# core3.net
KiCad netlist of a schematic drawn in EAGLE
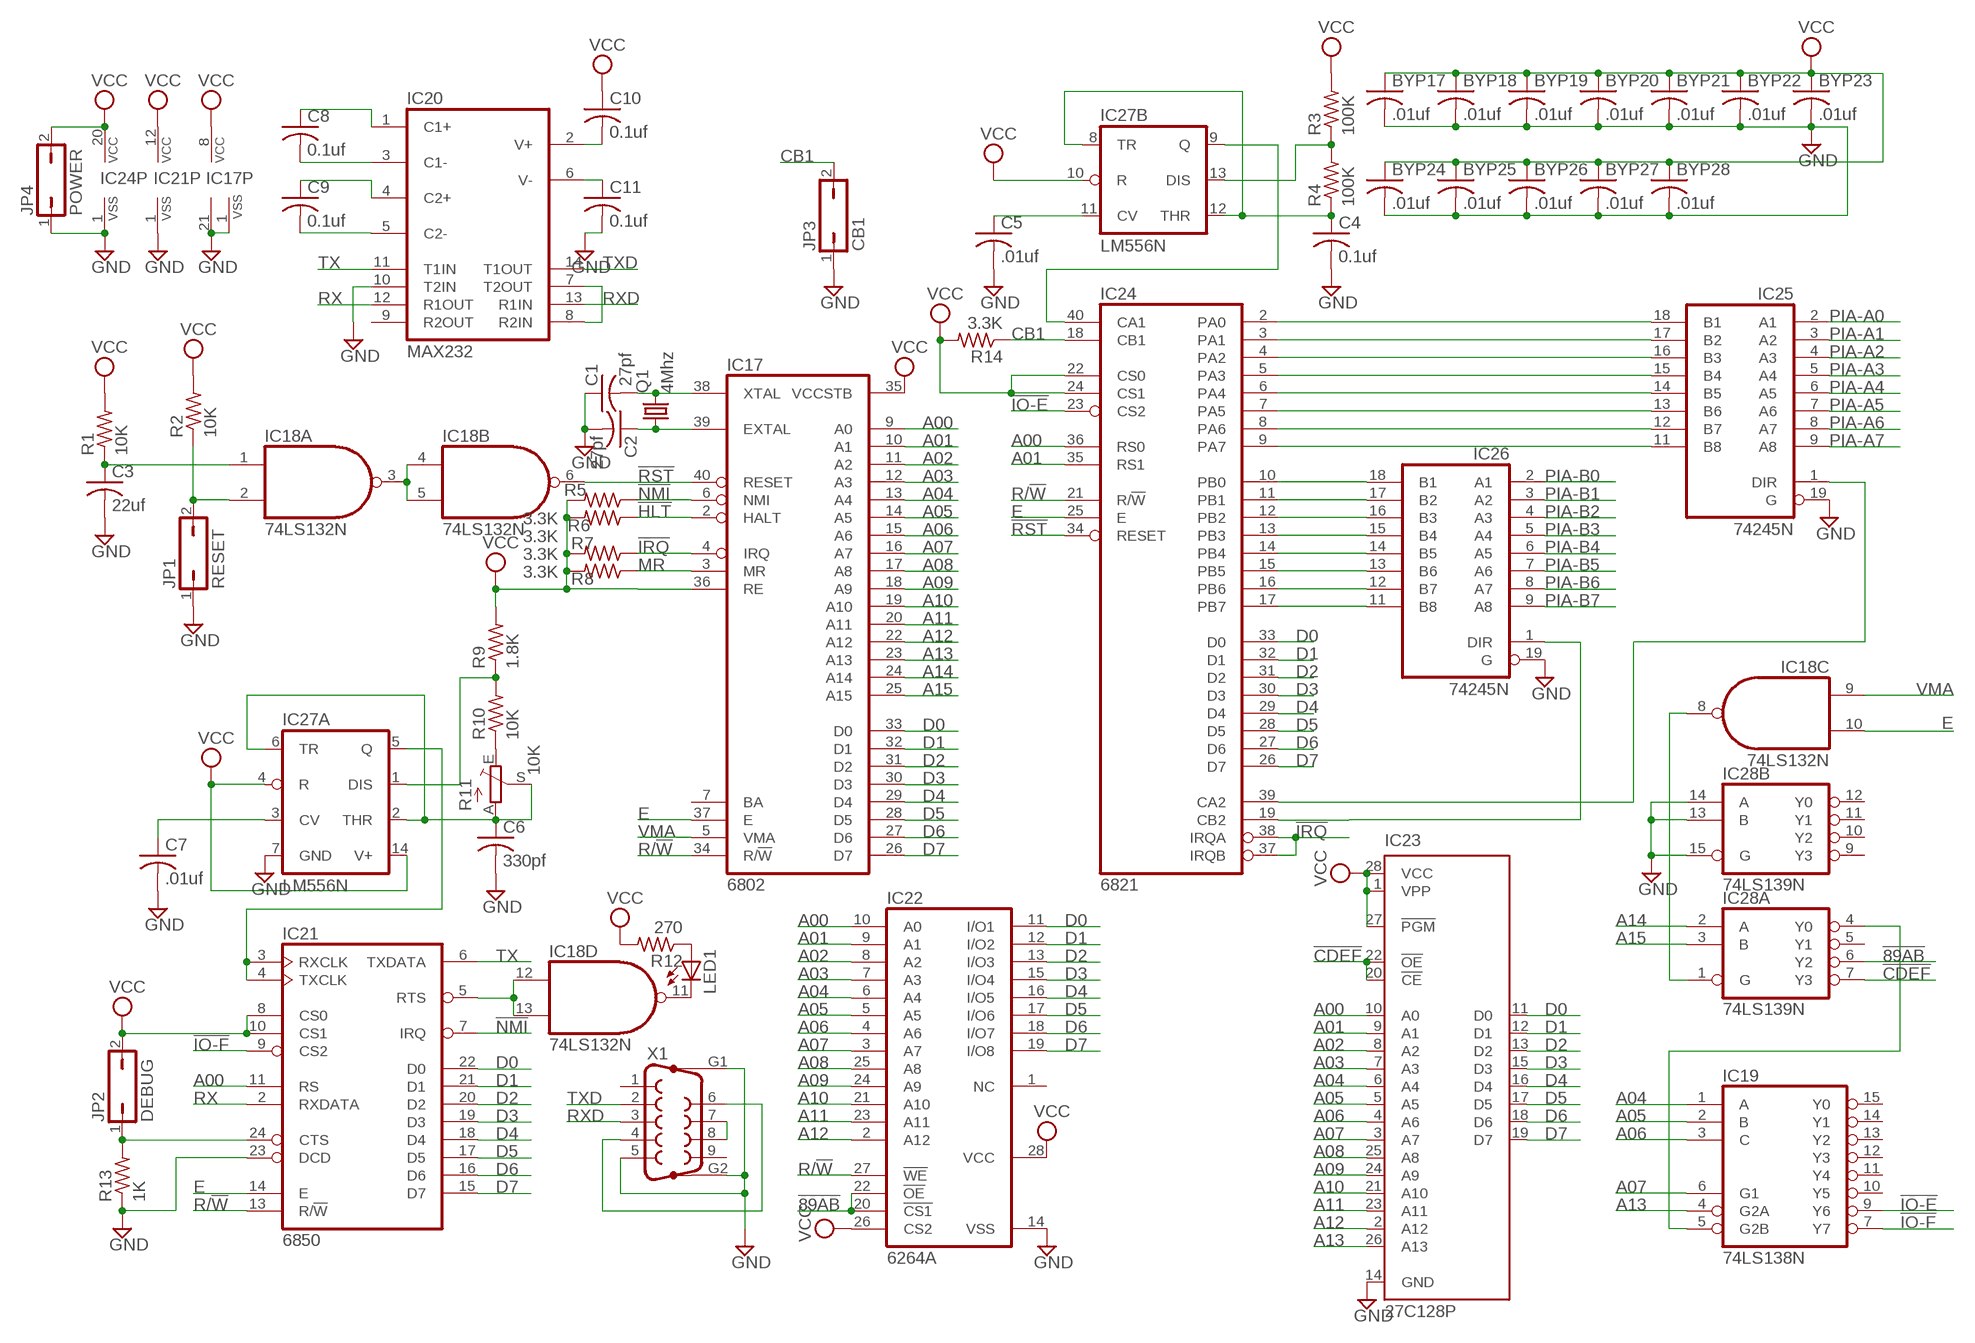
[diagram p0: schematic, sheet 1]
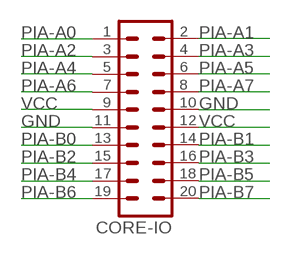
[diagram p1: schematic, sheet 2]

(export (version "E")
  (design (tool "Eeschema 10.0.6"))
  (components
    (comp (ref "BYP17")
      (value ".01uf")
      (footprint "eagle-import:C050-025X075")
      (libsource (lib "eagle-import") (part "C-US050-025X075"))
    )
    (comp (ref "BYP18")
      (value ".01uf")
      (footprint "eagle-import:C050-025X075")
      (libsource (lib "eagle-import") (part "C-US050-025X075"))
    )
    (comp (ref "BYP19")
      (value ".01uf")
      (footprint "eagle-import:C050-025X075")
      (libsource (lib "eagle-import") (part "C-US050-025X075"))
    )
    (comp (ref "BYP20")
      (value ".01uf")
      (footprint "eagle-import:C050-025X075")
      (libsource (lib "eagle-import") (part "C-US050-025X075"))
    )
    (comp (ref "BYP21")
      (value ".01uf")
      (footprint "eagle-import:C050-025X075")
      (libsource (lib "eagle-import") (part "C-US050-025X075"))
    )
    (comp (ref "BYP22")
      (value ".01uf")
      (footprint "eagle-import:C050-025X075")
      (libsource (lib "eagle-import") (part "C-US050-025X075"))
    )
    (comp (ref "BYP23")
      (value ".01uf")
      (footprint "eagle-import:C050-025X075")
      (libsource (lib "eagle-import") (part "C-US050-025X075"))
    )
    (comp (ref "BYP24")
      (value ".01uf")
      (footprint "eagle-import:C050-025X075")
      (libsource (lib "eagle-import") (part "C-US050-025X075"))
    )
    (comp (ref "BYP25")
      (value ".01uf")
      (footprint "eagle-import:C050-025X075")
      (libsource (lib "eagle-import") (part "C-US050-025X075"))
    )
    (comp (ref "BYP26")
      (value ".01uf")
      (footprint "eagle-import:C050-025X075")
      (libsource (lib "eagle-import") (part "C-US050-025X075"))
    )
    (comp (ref "BYP27")
      (value ".01uf")
      (footprint "eagle-import:C050-025X075")
      (libsource (lib "eagle-import") (part "C-US050-025X075"))
    )
    (comp (ref "BYP28")
      (value ".01uf")
      (footprint "eagle-import:C050-025X075")
      (libsource (lib "eagle-import") (part "C-US050-025X075"))
    )
    (comp (ref "C1")
      (value "27pf")
      (footprint "eagle-import:C050-025X075")
      (libsource (lib "eagle-import") (part "C-US050-025X075"))
    )
    (comp (ref "C2")
      (value "27pf")
      (footprint "eagle-import:C050-025X075")
      (libsource (lib "eagle-import") (part "C-US050-025X075"))
    )
    (comp (ref "C3")
      (value "22uf")
      (footprint "eagle-import:C102-043X133")
      (libsource (lib "eagle-import") (part "C-US102-043X133"))
    )
    (comp (ref "C4")
      (value "0.1uf")
      (footprint "eagle-import:C050-025X075")
      (libsource (lib "eagle-import") (part "C-US050-025X075"))
    )
    (comp (ref "C5")
      (value ".01uf")
      (footprint "eagle-import:C050-025X075")
      (libsource (lib "eagle-import") (part "C-US050-025X075"))
    )
    (comp (ref "C6")
      (value "330pf")
      (footprint "eagle-import:C050-025X075")
      (libsource (lib "eagle-import") (part "C-US050-025X075"))
    )
    (comp (ref "C7")
      (value ".01uf")
      (footprint "eagle-import:C050-025X075")
      (libsource (lib "eagle-import") (part "C-US050-025X075"))
    )
    (comp (ref "C8")
      (value "0.1uf")
      (footprint "eagle-import:C050-025X075")
      (libsource (lib "eagle-import") (part "C-US050-025X075"))
    )
    (comp (ref "C9")
      (value "0.1uf")
      (footprint "eagle-import:C050-025X075")
      (libsource (lib "eagle-import") (part "C-US050-025X075"))
    )
    (comp (ref "C10")
      (value "0.1uf")
      (footprint "eagle-import:C050-025X075")
      (libsource (lib "eagle-import") (part "C-US050-025X075"))
    )
    (comp (ref "C11")
      (value "0.1uf")
      (footprint "eagle-import:C050-025X075")
      (libsource (lib "eagle-import") (part "C-US050-025X075"))
    )
    (comp (ref "IC17")
      (value "6802")
      (footprint "eagle-import:DIL40")
      (libsource (lib "eagle-import") (part "6802"))
    )
    (comp (ref "IC18")
      (value "74LS132N")
      (footprint "eagle-import:DIL14")
      (libsource (lib "eagle-import") (part "7400NLS"))
    )
    (comp (ref "IC19")
      (value "74LS138N")
      (footprint "eagle-import:DIL16")
      (libsource (lib "eagle-import") (part "74138NLS"))
    )
    (comp (ref "IC20")
      (value "MAX232")
      (footprint "eagle-import:DIL16")
      (fields (field (name "MF") "MAXIM") (field (name "MPN") "MAX232ACPE+"))
      (libsource (lib "eagle-import") (part "MAX232"))
    )
    (comp (ref "IC21")
      (value "6850")
      (footprint "eagle-import:DIL24")
      (fields (field (name "MF") "NTE ELECTRONICS") (field (name "MPN") "NTE6850"))
      (libsource (lib "eagle-import") (part "6850"))
    )
    (comp (ref "IC22")
      (value "6264A")
      (footprint "eagle-import:DIL28-6")
      (libsource (lib "eagle-import") (part "6264A"))
    )
    (comp (ref "IC23")
      (value "27C128P")
      (footprint "eagle-import:DIL28-6")
      (libsource (lib "eagle-import") (part "27128PC"))
    )
    (comp (ref "IC24")
      (value "6821")
      (footprint "eagle-import:DIL40")
      (fields (field (name "MF") "NTE ELECTRONICS") (field (name "MPN") "NTE6821"))
      (libsource (lib "eagle-import") (part "6821"))
    )
    (comp (ref "IC25")
      (value "74245N")
      (footprint "eagle-import:DIL20")
      (libsource (lib "eagle-import") (part "74245NLS"))
    )
    (comp (ref "IC26")
      (value "74245N")
      (footprint "eagle-import:DIL20")
      (libsource (lib "eagle-import") (part "74245NLS"))
    )
    (comp (ref "IC27")
      (value "LM556N")
      (footprint "eagle-import:DIL14")
      (libsource (lib "eagle-import") (part "556NLM"))
    )
    (comp (ref "IC28")
      (value "74LS139N")
      (footprint "eagle-import:DIL16")
      (libsource (lib "eagle-import") (part "74139NLS"))
    )
    (comp (ref "JP1")
      (value "RESET")
      (footprint "eagle-import:JP1")
      (libsource (lib "eagle-import") (part "JP1Q"))
    )
    (comp (ref "JP2")
      (value "DEBUG")
      (footprint "eagle-import:JP1")
      (libsource (lib "eagle-import") (part "JP1Q"))
    )
    (comp (ref "JP3")
      (value "CB1")
      (footprint "eagle-import:JP1")
      (libsource (lib "eagle-import") (part "JP1Q"))
    )
    (comp (ref "JP4")
      (value "POWER")
      (footprint "eagle-import:JP1")
      (libsource (lib "eagle-import") (part "JP1Q"))
    )
    (comp (ref "LED1")
      (value "LED3MM")
      (footprint "eagle-import:LED3MM")
      (libsource (lib "eagle-import") (part "LED3MM"))
    )
    (comp (ref "Q1")
      (value "4Mhz")
      (footprint "eagle-import:HC18U-V")
      (libsource (lib "eagle-import") (part "CRYSTALHC18U-V"))
    )
    (comp (ref "R1")
      (value "10K")
      (footprint "eagle-import:0207_7")
      (libsource (lib "eagle-import") (part "R-US_0207/7"))
    )
    (comp (ref "R2")
      (value "10K")
      (footprint "eagle-import:0207_7")
      (libsource (lib "eagle-import") (part "R-US_0207/7"))
    )
    (comp (ref "R3")
      (value "100K")
      (footprint "eagle-import:0207_7")
      (libsource (lib "eagle-import") (part "R-US_0207/7"))
    )
    (comp (ref "R4")
      (value "100K")
      (footprint "eagle-import:0207_7")
      (libsource (lib "eagle-import") (part "R-US_0207/7"))
    )
    (comp (ref "R5")
      (value "3.3K")
      (footprint "eagle-import:0207_7")
      (libsource (lib "eagle-import") (part "R-US_0207/7"))
    )
    (comp (ref "R6")
      (value "3.3K")
      (footprint "eagle-import:0207_7")
      (libsource (lib "eagle-import") (part "R-US_0207/7"))
    )
    (comp (ref "R7")
      (value "3.3K")
      (footprint "eagle-import:0207_7")
      (libsource (lib "eagle-import") (part "R-US_0207/7"))
    )
    (comp (ref "R8")
      (value "3.3K")
      (footprint "eagle-import:0207_7")
      (libsource (lib "eagle-import") (part "R-US_0207/7"))
    )
    (comp (ref "R9")
      (value "1.8K")
      (footprint "eagle-import:0207_7")
      (libsource (lib "eagle-import") (part "R-US_0207/7"))
    )
    (comp (ref "R10")
      (value "10K")
      (footprint "eagle-import:0207_7")
      (libsource (lib "eagle-import") (part "R-US_0207/7"))
    )
    (comp (ref "R11")
      (value "10K")
      (footprint "eagle-import:SP19L")
      (libsource (lib "eagle-import") (part "TRIM_EU-B90P"))
    )
    (comp (ref "R12")
      (value "270")
      (footprint "eagle-import:0207_7")
      (libsource (lib "eagle-import") (part "R-US_0207/7"))
    )
    (comp (ref "R13")
      (value "1K")
      (footprint "eagle-import:0207_7")
      (libsource (lib "eagle-import") (part "R-US_0207/7"))
    )
    (comp (ref "R14")
      (value "3.3K")
      (footprint "eagle-import:0207_7")
      (libsource (lib "eagle-import") (part "R-US_0207/7"))
    )
    (comp (ref "X1")
      (value "F09HP")
      (footprint "eagle-import:F09HP")
      (libsource (lib "eagle-import") (part "F09HP"))
    )
    (comp (ref "CORE-IO")
      (value "MA10-2")
      (footprint "eagle-import:MA10-2")
      (libsource (lib "eagle-import") (part "MA10-2"))
    )
  )
  (nets
    (net (code "1") (name "A00") (class "Default")
      (node (ref "IC17") (pin "9") (pinfunction "A0_9") (pintype "output"))
      (node (ref "IC21") (pin "11") (pinfunction "RS_11") (pintype "input"))
      (node (ref "IC22") (pin "10") (pinfunction "A0_10") (pintype "input"))
      (node (ref "IC23") (pin "10") (pinfunction "A0_10") (pintype "input"))
      (node (ref "IC24") (pin "36") (pinfunction "RS0_36") (pintype "input"))
    )
    (net (code "2") (name "A01") (class "Default")
      (node (ref "IC17") (pin "10") (pinfunction "A1_10") (pintype "output"))
      (node (ref "IC22") (pin "9") (pinfunction "A1_9") (pintype "input"))
      (node (ref "IC23") (pin "9") (pinfunction "A1_9") (pintype "input"))
      (node (ref "IC24") (pin "35") (pinfunction "RS1_35") (pintype "input"))
    )
    (net (code "3") (name "A02") (class "Default")
      (node (ref "IC17") (pin "11") (pinfunction "A2_11") (pintype "output"))
      (node (ref "IC22") (pin "8") (pinfunction "A2_8") (pintype "input"))
      (node (ref "IC23") (pin "8") (pinfunction "A2_8") (pintype "input"))
    )
    (net (code "4") (name "A03") (class "Default")
      (node (ref "IC17") (pin "12") (pinfunction "A3_12") (pintype "output"))
      (node (ref "IC22") (pin "7") (pinfunction "A3_7") (pintype "input"))
      (node (ref "IC23") (pin "7") (pinfunction "A3_7") (pintype "input"))
    )
    (net (code "5") (name "A04") (class "Default")
      (node (ref "IC17") (pin "13") (pinfunction "A4_13") (pintype "output"))
      (node (ref "IC19") (pin "1") (pinfunction "A_1") (pintype "input"))
      (node (ref "IC22") (pin "6") (pinfunction "A4_6") (pintype "input"))
      (node (ref "IC23") (pin "6") (pinfunction "A4_6") (pintype "input"))
    )
    (net (code "6") (name "A05") (class "Default")
      (node (ref "IC17") (pin "14") (pinfunction "A5_14") (pintype "output"))
      (node (ref "IC19") (pin "2") (pinfunction "B_2") (pintype "input"))
      (node (ref "IC22") (pin "5") (pinfunction "A5_5") (pintype "input"))
      (node (ref "IC23") (pin "5") (pinfunction "A5_5") (pintype "input"))
    )
    (net (code "7") (name "A06") (class "Default")
      (node (ref "IC17") (pin "15") (pinfunction "A6_15") (pintype "output"))
      (node (ref "IC19") (pin "3") (pinfunction "C_3") (pintype "input"))
      (node (ref "IC22") (pin "4") (pinfunction "A6_4") (pintype "input"))
      (node (ref "IC23") (pin "4") (pinfunction "A6_4") (pintype "input"))
    )
    (net (code "8") (name "A07") (class "Default")
      (node (ref "IC17") (pin "16") (pinfunction "A7_16") (pintype "output"))
      (node (ref "IC19") (pin "6") (pinfunction "G1_6") (pintype "input"))
      (node (ref "IC22") (pin "3") (pinfunction "A7_3") (pintype "input"))
      (node (ref "IC23") (pin "3") (pinfunction "A7_3") (pintype "input"))
    )
    (net (code "9") (name "A08") (class "Default")
      (node (ref "IC17") (pin "17") (pinfunction "A8_17") (pintype "output"))
      (node (ref "IC22") (pin "25") (pinfunction "A8_25") (pintype "input"))
      (node (ref "IC23") (pin "25") (pinfunction "A8_25") (pintype "input"))
    )
    (net (code "10") (name "A09") (class "Default")
      (node (ref "IC17") (pin "18") (pinfunction "A9_18") (pintype "output"))
      (node (ref "IC22") (pin "24") (pinfunction "A9_24") (pintype "input"))
      (node (ref "IC23") (pin "24") (pinfunction "A9_24") (pintype "input"))
    )
    (net (code "11") (name "A10") (class "Default")
      (node (ref "IC17") (pin "19") (pinfunction "A10_19") (pintype "output"))
      (node (ref "IC22") (pin "21") (pinfunction "A10_21") (pintype "input"))
      (node (ref "IC23") (pin "21") (pinfunction "A10_21") (pintype "input"))
    )
    (net (code "12") (name "A11") (class "Default")
      (node (ref "IC17") (pin "20") (pinfunction "A11_20") (pintype "output"))
      (node (ref "IC22") (pin "23") (pinfunction "A11_23") (pintype "input"))
      (node (ref "IC23") (pin "23") (pinfunction "A11_23") (pintype "input"))
    )
    (net (code "13") (name "A12") (class "Default")
      (node (ref "IC17") (pin "22") (pinfunction "A12_22") (pintype "output"))
      (node (ref "IC22") (pin "2") (pinfunction "A12_2") (pintype "input"))
      (node (ref "IC23") (pin "2") (pinfunction "A12_2") (pintype "input"))
    )
    (net (code "14") (name "A13") (class "Default")
      (node (ref "IC17") (pin "23") (pinfunction "A13_23") (pintype "output"))
      (node (ref "IC19") (pin "4") (pinfunction "G2A_4") (pintype "input"))
      (node (ref "IC23") (pin "26") (pinfunction "A13_26") (pintype "input"))
    )
    (net (code "15") (name "A14") (class "Default")
      (node (ref "IC17") (pin "24") (pinfunction "A14_24") (pintype "output"))
      (node (ref "IC28") (pin "2") (pinfunction "A_2") (pintype "input"))
    )
    (net (code "16") (name "A15") (class "Default")
      (node (ref "IC17") (pin "25") (pinfunction "A15_25") (pintype "output"))
      (node (ref "IC28") (pin "3") (pinfunction "B_3") (pintype "input"))
    )
    (net (code "17") (name "CB1") (class "Default")
      (node (ref "IC24") (pin "18") (pinfunction "CB1_18") (pintype "input"))
      (node (ref "JP3") (pin "2") (pinfunction "2_2") (pintype "passive"))
      (node (ref "R14") (pin "1") (pinfunction "1_1") (pintype "passive"))
    )
    (net (code "18") (name "D0") (class "Default")
      (node (ref "IC17") (pin "33") (pinfunction "D0_33") (pintype "bidirectional"))
      (node (ref "IC21") (pin "22") (pinfunction "D0_22") (pintype "bidirectional"))
      (node (ref "IC22") (pin "11") (pinfunction "I/O1_11") (pintype "bidirectional"))
      (node (ref "IC23") (pin "11") (pinfunction "D0_11") (pintype "tri_state"))
      (node (ref "IC24") (pin "33") (pinfunction "D0_33") (pintype "bidirectional"))
    )
    (net (code "19") (name "D1") (class "Default")
      (node (ref "IC17") (pin "32") (pinfunction "D1_32") (pintype "bidirectional"))
      (node (ref "IC21") (pin "21") (pinfunction "D1_21") (pintype "bidirectional"))
      (node (ref "IC22") (pin "12") (pinfunction "I/O2_12") (pintype "bidirectional"))
      (node (ref "IC23") (pin "12") (pinfunction "D1_12") (pintype "tri_state"))
      (node (ref "IC24") (pin "32") (pinfunction "D1_32") (pintype "bidirectional"))
    )
    (net (code "20") (name "D2") (class "Default")
      (node (ref "IC17") (pin "31") (pinfunction "D2_31") (pintype "bidirectional"))
      (node (ref "IC21") (pin "20") (pinfunction "D2_20") (pintype "bidirectional"))
      (node (ref "IC22") (pin "13") (pinfunction "I/O3_13") (pintype "bidirectional"))
      (node (ref "IC23") (pin "13") (pinfunction "D2_13") (pintype "tri_state"))
      (node (ref "IC24") (pin "31") (pinfunction "D2_31") (pintype "bidirectional"))
    )
    (net (code "21") (name "D3") (class "Default")
      (node (ref "IC17") (pin "30") (pinfunction "D3_30") (pintype "bidirectional"))
      (node (ref "IC21") (pin "19") (pinfunction "D3_19") (pintype "bidirectional"))
      (node (ref "IC22") (pin "15") (pinfunction "I/O4_15") (pintype "bidirectional"))
      (node (ref "IC23") (pin "15") (pinfunction "D3_15") (pintype "tri_state"))
      (node (ref "IC24") (pin "30") (pinfunction "D3_30") (pintype "bidirectional"))
    )
    (net (code "22") (name "D4") (class "Default")
      (node (ref "IC17") (pin "29") (pinfunction "D4_29") (pintype "bidirectional"))
      (node (ref "IC21") (pin "18") (pinfunction "D4_18") (pintype "bidirectional"))
      (node (ref "IC22") (pin "16") (pinfunction "I/O5_16") (pintype "bidirectional"))
      (node (ref "IC23") (pin "16") (pinfunction "D4_16") (pintype "tri_state"))
      (node (ref "IC24") (pin "29") (pinfunction "D4_29") (pintype "bidirectional"))
    )
    (net (code "23") (name "D5") (class "Default")
      (node (ref "IC17") (pin "28") (pinfunction "D5_28") (pintype "bidirectional"))
      (node (ref "IC21") (pin "17") (pinfunction "D5_17") (pintype "bidirectional"))
      (node (ref "IC22") (pin "17") (pinfunction "I/O6_17") (pintype "bidirectional"))
      (node (ref "IC23") (pin "17") (pinfunction "D5_17") (pintype "tri_state"))
      (node (ref "IC24") (pin "28") (pinfunction "D5_28") (pintype "bidirectional"))
    )
    (net (code "24") (name "D6") (class "Default")
      (node (ref "IC17") (pin "27") (pinfunction "D6_27") (pintype "bidirectional"))
      (node (ref "IC21") (pin "16") (pinfunction "D6_16") (pintype "bidirectional"))
      (node (ref "IC22") (pin "18") (pinfunction "I/O7_18") (pintype "bidirectional"))
      (node (ref "IC23") (pin "18") (pinfunction "D6_18") (pintype "tri_state"))
      (node (ref "IC24") (pin "27") (pinfunction "D6_27") (pintype "bidirectional"))
    )
    (net (code "25") (name "D7") (class "Default")
      (node (ref "IC17") (pin "26") (pinfunction "D7_26") (pintype "bidirectional"))
      (node (ref "IC21") (pin "15") (pinfunction "D7_15") (pintype "bidirectional"))
      (node (ref "IC22") (pin "19") (pinfunction "I/O8_19") (pintype "bidirectional"))
      (node (ref "IC23") (pin "19") (pinfunction "D7_19") (pintype "tri_state"))
      (node (ref "IC24") (pin "26") (pinfunction "D7_26") (pintype "bidirectional"))
    )
    (net (code "26") (name "E") (class "Default")
      (node (ref "IC17") (pin "37") (pinfunction "E_37") (pintype "output"))
      (node (ref "IC18") (pin "10") (pinfunction "I1_10") (pintype "input"))
      (node (ref "IC21") (pin "14") (pinfunction "E_14") (pintype "input"))
      (node (ref "IC24") (pin "25") (pinfunction "E_25") (pintype "input"))
    )
    (net (code "27") (name "GND") (class "Default")
      (node (ref "BYP17") (pin "2") (pinfunction "2_2") (pintype "passive"))
      (node (ref "BYP18") (pin "2") (pinfunction "2_2") (pintype "passive"))
      (node (ref "BYP19") (pin "2") (pinfunction "2_2") (pintype "passive"))
      (node (ref "BYP20") (pin "2") (pinfunction "2_2") (pintype "passive"))
      (node (ref "BYP21") (pin "2") (pinfunction "2_2") (pintype "passive"))
      (node (ref "BYP22") (pin "2") (pinfunction "2_2") (pintype "passive"))
      (node (ref "BYP23") (pin "2") (pinfunction "2_2") (pintype "passive"))
      (node (ref "BYP24") (pin "2") (pinfunction "2_2") (pintype "passive"))
      (node (ref "BYP25") (pin "2") (pinfunction "2_2") (pintype "passive"))
      (node (ref "BYP26") (pin "2") (pinfunction "2_2") (pintype "passive"))
      (node (ref "BYP27") (pin "2") (pinfunction "2_2") (pintype "passive"))
      (node (ref "BYP28") (pin "2") (pinfunction "2_2") (pintype "passive"))
      (node (ref "C1") (pin "1") (pinfunction "1_1") (pintype "passive"))
      (node (ref "C11") (pin "2") (pinfunction "2_2") (pintype "passive"))
      (node (ref "C2") (pin "2") (pinfunction "2_2") (pintype "passive"))
      (node (ref "C3") (pin "2") (pinfunction "2_2") (pintype "passive"))
      (node (ref "C4") (pin "2") (pinfunction "2_2") (pintype "passive"))
      (node (ref "C5") (pin "2") (pinfunction "2_2") (pintype "passive"))
      (node (ref "C6") (pin "2") (pinfunction "2_2") (pintype "passive"))
      (node (ref "C7") (pin "2") (pinfunction "2_2") (pintype "passive"))
      (node (ref "CORE-IO") (pin "10") (pinfunction "10_10") (pintype "passive"))
      (node (ref "CORE-IO") (pin "11") (pinfunction "11_11") (pintype "passive"))
      (node (ref "IC17") (pin "1") (pinfunction "VSS_1") (pintype "power_in"))
      (node (ref "IC17") (pin "21") (pinfunction "VSS_21") (pintype "power_in"))
      (node (ref "IC20") (pin "10") (pinfunction "T2IN_10") (pintype "input"))
      (node (ref "IC21") (pin "1") (pinfunction "VSS_1") (pintype "power_in"))
      (node (ref "IC21") (pin "23") (pinfunction "DCD_23") (pintype "input"))
      (node (ref "IC22") (pin "14") (pinfunction "VSS_14") (pintype "power_in"))
      (node (ref "IC23") (pin "14") (pinfunction "GND_14") (pintype "power_in"))
      (node (ref "IC24") (pin "1") (pinfunction "VSS_1") (pintype "power_in"))
      (node (ref "IC25") (pin "19") (pinfunction "G_19") (pintype "input"))
      (node (ref "IC26") (pin "19") (pinfunction "G_19") (pintype "input"))
      (node (ref "IC27") (pin "7") (pinfunction "GND_7") (pintype "power_in"))
      (node (ref "IC28") (pin "13") (pinfunction "B_13") (pintype "input"))
      (node (ref "IC28") (pin "14") (pinfunction "A_14") (pintype "input"))
      (node (ref "IC28") (pin "15") (pinfunction "G_15") (pintype "input"))
      (node (ref "JP1") (pin "1") (pinfunction "1_1") (pintype "passive"))
      (node (ref "JP3") (pin "1") (pinfunction "1_1") (pintype "passive"))
      (node (ref "JP4") (pin "1") (pinfunction "1_1") (pintype "passive"))
      (node (ref "R13") (pin "1") (pinfunction "1_1") (pintype "passive"))
      (node (ref "X1") (pin "5") (pinfunction "5_5") (pintype "passive"))
      (node (ref "X1") (pin "G1") (pinfunction "G1_G1") (pintype "passive"))
      (node (ref "X1") (pin "G2") (pinfunction "G2_G2") (pintype "passive"))
    )
    (net (code "28") (name "MR") (class "Default")
      (node (ref "IC17") (pin "3") (pinfunction "MR_3") (pintype "input"))
      (node (ref "R8") (pin "1") (pinfunction "1_1") (pintype "passive"))
    )
    (net (code "29") (name "Net-(IC17A-EXTAL)") (class "Default")
      (node (ref "C2") (pin "1") (pinfunction "1_1") (pintype "passive"))
      (node (ref "IC17") (pin "39") (pinfunction "EXTAL_39") (pintype "input"))
      (node (ref "Q1") (pin "1") (pinfunction "1_1") (pintype "passive"))
    )
    (net (code "30") (name "Net-(IC17A-XTAL)") (class "Default")
      (node (ref "C1") (pin "2") (pinfunction "2_2") (pintype "passive"))
      (node (ref "IC17") (pin "38") (pinfunction "XTAL_38") (pintype "input"))
      (node (ref "Q1") (pin "2") (pinfunction "2_2") (pintype "passive"))
    )
    (net (code "31") (name "Net-(IC18A-I0)") (class "Default")
      (node (ref "C3") (pin "1") (pinfunction "1_1") (pintype "passive"))
      (node (ref "IC18") (pin "1") (pinfunction "I0_1") (pintype "input"))
      (node (ref "R1") (pin "1") (pinfunction "1_1") (pintype "passive"))
    )
    (net (code "32") (name "Net-(IC18A-I1)") (class "Default")
      (node (ref "IC18") (pin "2") (pinfunction "I1_2") (pintype "input"))
      (node (ref "JP1") (pin "2") (pinfunction "2_2") (pintype "passive"))
      (node (ref "R2") (pin "1") (pinfunction "1_1") (pintype "passive"))
    )
    (net (code "33") (name "Net-(IC18A-O)") (class "Default")
      (node (ref "IC18") (pin "3") (pinfunction "O_3") (pintype "output"))
      (node (ref "IC18") (pin "4") (pinfunction "I0_4") (pintype "input"))
      (node (ref "IC18") (pin "5") (pinfunction "I1_5") (pintype "input"))
    )
    (net (code "34") (name "Net-(IC18C-O)") (class "Default")
      (node (ref "IC18") (pin "8") (pinfunction "O_8") (pintype "output"))
      (node (ref "IC28") (pin "1") (pinfunction "G_1") (pintype "input"))
    )
    (net (code "35") (name "Net-(IC18D-I0)") (class "Default")
      (node (ref "IC18") (pin "12") (pinfunction "I0_12") (pintype "input"))
      (node (ref "IC18") (pin "13") (pinfunction "I1_13") (pintype "input"))
      (node (ref "IC21") (pin "5") (pinfunction "RTS_5") (pintype "output"))
    )
    (net (code "36") (name "Net-(IC18D-O)") (class "Default")
      (node (ref "IC18") (pin "11") (pinfunction "O_11") (pintype "output"))
      (node (ref "LED1") (pin "K") (pinfunction "C_K") (pintype "passive"))
    )
    (net (code "37") (name "Net-(IC19A-G2B)") (class "Default")
      (node (ref "IC19") (pin "5") (pinfunction "G2B_5") (pintype "input"))
      (node (ref "IC28") (pin "4") (pinfunction "Y0_4") (pintype "output"))
    )
    (net (code "38") (name "Net-(IC20A-C1+)") (class "Default")
      (node (ref "C8") (pin "1") (pinfunction "1_1") (pintype "passive"))
      (node (ref "IC20") (pin "1") (pinfunction "C1+_1") (pintype "bidirectional"))
    )
    (net (code "39") (name "Net-(IC20A-C1-)") (class "Default")
      (node (ref "C8") (pin "2") (pinfunction "2_2") (pintype "passive"))
      (node (ref "IC20") (pin "3") (pinfunction "C1-_3") (pintype "bidirectional"))
    )
    (net (code "40") (name "Net-(IC20A-C2+)") (class "Default")
      (node (ref "C9") (pin "1") (pinfunction "1_1") (pintype "passive"))
      (node (ref "IC20") (pin "4") (pinfunction "C2+_4") (pintype "bidirectional"))
    )
    (net (code "41") (name "Net-(IC20A-C2-)") (class "Default")
      (node (ref "C9") (pin "2") (pinfunction "2_2") (pintype "passive"))
      (node (ref "IC20") (pin "5") (pinfunction "C2-_5") (pintype "bidirectional"))
    )
    (net (code "42") (name "Net-(IC20A-R2IN)") (class "Default")
      (node (ref "IC20") (pin "7") (pinfunction "T2OUT_7") (pintype "output"))
      (node (ref "IC20") (pin "8") (pinfunction "R2IN_8") (pintype "input"))
    )
    (net (code "43") (name "Net-(IC20A-V+)") (class "Default")
      (node (ref "C10") (pin "2") (pinfunction "2_2") (pintype "passive"))
      (node (ref "IC20") (pin "2") (pinfunction "V+_2") (pintype "bidirectional"))
    )
    (net (code "44") (name "Net-(IC20A-V-)") (class "Default")
      (node (ref "C11") (pin "1") (pinfunction "1_1") (pintype "passive"))
      (node (ref "IC20") (pin "6") (pinfunction "V-_6") (pintype "bidirectional"))
    )
    (net (code "45") (name "Net-(IC21A-CTS)") (class "Default")
      (node (ref "IC21") (pin "24") (pinfunction "CTS_24") (pintype "input"))
      (node (ref "JP2") (pin "1") (pinfunction "1_1") (pintype "passive"))
      (node (ref "R13") (pin "2") (pinfunction "2_2") (pintype "passive"))
    )
    (net (code "46") (name "Net-(IC21A-RXCLK)") (class "Default")
      (node (ref "IC21") (pin "3") (pinfunction "RXCLK_3") (pintype "input"))
      (node (ref "IC21") (pin "4") (pinfunction "TXCLK_4") (pintype "input"))
      (node (ref "IC27") (pin "5") (pinfunction "Q_5") (pintype "output"))
    )
    (net (code "47") (name "Net-(IC24A-CA1)") (class "Default")
      (node (ref "IC24") (pin "40") (pinfunction "CA1_40") (pintype "input"))
      (node (ref "IC27") (pin "9") (pinfunction "Q_9") (pintype "output"))
    )
    (net (code "48") (name "Net-(IC24A-CA2)") (class "Default")
      (node (ref "IC24") (pin "39") (pinfunction "CA2_39") (pintype "bidirectional"))
      (node (ref "IC25") (pin "1") (pinfunction "DIR_1") (pintype "input"))
    )
    (net (code "49") (name "Net-(IC24A-CB2)") (class "Default")
      (node (ref "IC24") (pin "19") (pinfunction "CB2_19") (pintype "bidirectional"))
      (node (ref "IC26") (pin "1") (pinfunction "DIR_1") (pintype "input"))
    )
    (net (code "50") (name "Net-(IC24A-PA0)") (class "Default")
      (node (ref "IC24") (pin "2") (pinfunction "PA0_2") (pintype "bidirectional"))
      (node (ref "IC25") (pin "18") (pinfunction "B1_18") (pintype "bidirectional"))
    )
    (net (code "51") (name "Net-(IC24A-PA1)") (class "Default")
      (node (ref "IC24") (pin "3") (pinfunction "PA1_3") (pintype "bidirectional"))
      (node (ref "IC25") (pin "17") (pinfunction "B2_17") (pintype "bidirectional"))
    )
    (net (code "52") (name "Net-(IC24A-PA2)") (class "Default")
      (node (ref "IC24") (pin "4") (pinfunction "PA2_4") (pintype "bidirectional"))
      (node (ref "IC25") (pin "16") (pinfunction "B3_16") (pintype "bidirectional"))
    )
    (net (code "53") (name "Net-(IC24A-PA3)") (class "Default")
      (node (ref "IC24") (pin "5") (pinfunction "PA3_5") (pintype "bidirectional"))
      (node (ref "IC25") (pin "15") (pinfunction "B4_15") (pintype "bidirectional"))
    )
    (net (code "54") (name "Net-(IC24A-PA4)") (class "Default")
      (node (ref "IC24") (pin "6") (pinfunction "PA4_6") (pintype "bidirectional"))
      (node (ref "IC25") (pin "14") (pinfunction "B5_14") (pintype "bidirectional"))
    )
    (net (code "55") (name "Net-(IC24A-PA5)") (class "Default")
      (node (ref "IC24") (pin "7") (pinfunction "PA5_7") (pintype "bidirectional"))
      (node (ref "IC25") (pin "13") (pinfunction "B6_13") (pintype "bidirectional"))
    )
    (net (code "56") (name "Net-(IC24A-PA6)") (class "Default")
      (node (ref "IC24") (pin "8") (pinfunction "PA6_8") (pintype "bidirectional"))
      (node (ref "IC25") (pin "12") (pinfunction "B7_12") (pintype "bidirectional"))
    )
    (net (code "57") (name "Net-(IC24A-PA7)") (class "Default")
      (node (ref "IC24") (pin "9") (pinfunction "PA7_9") (pintype "bidirectional"))
      (node (ref "IC25") (pin "11") (pinfunction "B8_11") (pintype "bidirectional"))
    )
    (net (code "58") (name "Net-(IC24A-PB0)") (class "Default")
      (node (ref "IC24") (pin "10") (pinfunction "PB0_10") (pintype "bidirectional"))
      (node (ref "IC26") (pin "18") (pinfunction "B1_18") (pintype "bidirectional"))
    )
    (net (code "59") (name "Net-(IC24A-PB1)") (class "Default")
      (node (ref "IC24") (pin "11") (pinfunction "PB1_11") (pintype "bidirectional"))
      (node (ref "IC26") (pin "17") (pinfunction "B2_17") (pintype "bidirectional"))
    )
    (net (code "60") (name "Net-(IC24A-PB2)") (class "Default")
      (node (ref "IC24") (pin "12") (pinfunction "PB2_12") (pintype "bidirectional"))
      (node (ref "IC26") (pin "16") (pinfunction "B3_16") (pintype "bidirectional"))
    )
    (net (code "61") (name "Net-(IC24A-PB3)") (class "Default")
      (node (ref "IC24") (pin "13") (pinfunction "PB3_13") (pintype "bidirectional"))
      (node (ref "IC26") (pin "15") (pinfunction "B4_15") (pintype "bidirectional"))
    )
    (net (code "62") (name "Net-(IC24A-PB4)") (class "Default")
      (node (ref "IC24") (pin "14") (pinfunction "PB4_14") (pintype "bidirectional"))
      (node (ref "IC26") (pin "14") (pinfunction "B5_14") (pintype "bidirectional"))
    )
    (net (code "63") (name "Net-(IC24A-PB5)") (class "Default")
      (node (ref "IC24") (pin "15") (pinfunction "PB5_15") (pintype "bidirectional"))
      (node (ref "IC26") (pin "13") (pinfunction "B6_13") (pintype "bidirectional"))
    )
    (net (code "64") (name "Net-(IC24A-PB6)") (class "Default")
      (node (ref "IC24") (pin "16") (pinfunction "PB6_16") (pintype "bidirectional"))
      (node (ref "IC26") (pin "12") (pinfunction "B7_12") (pintype "bidirectional"))
    )
    (net (code "65") (name "Net-(IC24A-PB7)") (class "Default")
      (node (ref "IC24") (pin "17") (pinfunction "PB7_17") (pintype "bidirectional"))
      (node (ref "IC26") (pin "11") (pinfunction "B8_11") (pintype "bidirectional"))
    )
    (net (code "66") (name "Net-(IC27A-CV)") (class "Default")
      (node (ref "C7") (pin "1") (pinfunction "1_1") (pintype "passive"))
      (node (ref "IC27") (pin "3") (pinfunction "CV_3") (pintype "input"))
    )
    (net (code "67") (name "Net-(IC27A-DIS)") (class "Default")
      (node (ref "IC27") (pin "1") (pinfunction "DIS_1") (pintype "input"))
      (node (ref "R10") (pin "2") (pinfunction "2_2") (pintype "passive"))
      (node (ref "R9") (pin "1") (pinfunction "1_1") (pintype "passive"))
    )
    (net (code "68") (name "Net-(IC27A-THR)") (class "Default")
      (node (ref "C6") (pin "1") (pinfunction "1_1") (pintype "passive"))
      (node (ref "IC27") (pin "2") (pinfunction "THR_2") (pintype "input"))
      (node (ref "IC27") (pin "6") (pinfunction "TR_6") (pintype "input"))
      (node (ref "R11") (pin "A") (pinfunction "A_A") (pintype "passive"))
      (node (ref "R11") (pin "S") (pinfunction "S_S") (pintype "passive"))
    )
    (net (code "69") (name "Net-(IC27B-CV)") (class "Default")
      (node (ref "C5") (pin "1") (pinfunction "1_1") (pintype "passive"))
      (node (ref "IC27") (pin "11") (pinfunction "CV_11") (pintype "input"))
    )
    (net (code "70") (name "Net-(IC27B-DIS)") (class "Default")
      (node (ref "IC27") (pin "13") (pinfunction "DIS_13") (pintype "input"))
      (node (ref "R3") (pin "1") (pinfunction "1_1") (pintype "passive"))
      (node (ref "R4") (pin "2") (pinfunction "2_2") (pintype "passive"))
    )
    (net (code "71") (name "Net-(IC27B-THR)") (class "Default")
      (node (ref "C4") (pin "1") (pinfunction "1_1") (pintype "passive"))
      (node (ref "IC27") (pin "12") (pinfunction "THR_12") (pintype "input"))
      (node (ref "IC27") (pin "8") (pinfunction "TR_8") (pintype "input"))
      (node (ref "R4") (pin "1") (pinfunction "1_1") (pintype "passive"))
    )
    (net (code "72") (name "Net-(LED1-PadA)") (class "Default")
      (node (ref "LED1") (pin "A") (pinfunction "A_A") (pintype "passive"))
      (node (ref "R12") (pin "1") (pinfunction "1_1") (pintype "passive"))
    )
    (net (code "73") (name "Net-(R10-Pad1)") (class "Default")
      (node (ref "R10") (pin "1") (pinfunction "1_1") (pintype "passive"))
      (node (ref "R11") (pin "E") (pinfunction "E_E") (pintype "passive"))
    )
    (net (code "74") (name "Net-(X1-Pad4)") (class "Default")
      (node (ref "X1") (pin "4") (pinfunction "4_4") (pintype "passive"))
      (node (ref "X1") (pin "6") (pinfunction "6_6") (pintype "passive"))
    )
    (net (code "75") (name "Net-(X1-Pad7)") (class "Default")
      (node (ref "X1") (pin "7") (pinfunction "7_7") (pintype "passive"))
      (node (ref "X1") (pin "8") (pinfunction "8_8") (pintype "passive"))
    )
    (net (code "76") (name "PIA-A0") (class "Default")
      (node (ref "CORE-IO") (pin "1") (pinfunction "1_1") (pintype "passive"))
      (node (ref "IC25") (pin "2") (pinfunction "A1_2") (pintype "bidirectional"))
    )
    (net (code "77") (name "PIA-A1") (class "Default")
      (node (ref "CORE-IO") (pin "2") (pinfunction "2_2") (pintype "passive"))
      (node (ref "IC25") (pin "3") (pinfunction "A2_3") (pintype "bidirectional"))
    )
    (net (code "78") (name "PIA-A2") (class "Default")
      (node (ref "CORE-IO") (pin "3") (pinfunction "3_3") (pintype "passive"))
      (node (ref "IC25") (pin "4") (pinfunction "A3_4") (pintype "bidirectional"))
    )
    (net (code "79") (name "PIA-A3") (class "Default")
      (node (ref "CORE-IO") (pin "4") (pinfunction "4_4") (pintype "passive"))
      (node (ref "IC25") (pin "5") (pinfunction "A4_5") (pintype "bidirectional"))
    )
    (net (code "80") (name "PIA-A4") (class "Default")
      (node (ref "CORE-IO") (pin "5") (pinfunction "5_5") (pintype "passive"))
      (node (ref "IC25") (pin "6") (pinfunction "A5_6") (pintype "bidirectional"))
    )
    (net (code "81") (name "PIA-A5") (class "Default")
      (node (ref "CORE-IO") (pin "6") (pinfunction "6_6") (pintype "passive"))
      (node (ref "IC25") (pin "7") (pinfunction "A6_7") (pintype "bidirectional"))
    )
    (net (code "82") (name "PIA-A6") (class "Default")
      (node (ref "CORE-IO") (pin "7") (pinfunction "7_7") (pintype "passive"))
      (node (ref "IC25") (pin "8") (pinfunction "A7_8") (pintype "bidirectional"))
    )
    (net (code "83") (name "PIA-A7") (class "Default")
      (node (ref "CORE-IO") (pin "8") (pinfunction "8_8") (pintype "passive"))
      (node (ref "IC25") (pin "9") (pinfunction "A8_9") (pintype "bidirectional"))
    )
    (net (code "84") (name "PIA-B0") (class "Default")
      (node (ref "CORE-IO") (pin "13") (pinfunction "13_13") (pintype "passive"))
      (node (ref "IC26") (pin "2") (pinfunction "A1_2") (pintype "bidirectional"))
    )
    (net (code "85") (name "PIA-B1") (class "Default")
      (node (ref "CORE-IO") (pin "14") (pinfunction "14_14") (pintype "passive"))
      (node (ref "IC26") (pin "3") (pinfunction "A2_3") (pintype "bidirectional"))
    )
    (net (code "86") (name "PIA-B2") (class "Default")
      (node (ref "CORE-IO") (pin "15") (pinfunction "15_15") (pintype "passive"))
      (node (ref "IC26") (pin "4") (pinfunction "A3_4") (pintype "bidirectional"))
    )
    (net (code "87") (name "PIA-B3") (class "Default")
      (node (ref "CORE-IO") (pin "16") (pinfunction "16_16") (pintype "passive"))
      (node (ref "IC26") (pin "5") (pinfunction "A4_5") (pintype "bidirectional"))
    )
    (net (code "88") (name "PIA-B4") (class "Default")
      (node (ref "CORE-IO") (pin "17") (pinfunction "17_17") (pintype "passive"))
      (node (ref "IC26") (pin "6") (pinfunction "A5_6") (pintype "bidirectional"))
    )
    (net (code "89") (name "PIA-B5") (class "Default")
      (node (ref "CORE-IO") (pin "18") (pinfunction "18_18") (pintype "passive"))
      (node (ref "IC26") (pin "7") (pinfunction "A6_7") (pintype "bidirectional"))
    )
    (net (code "90") (name "PIA-B6") (class "Default")
      (node (ref "CORE-IO") (pin "19") (pinfunction "19_19") (pintype "passive"))
      (node (ref "IC26") (pin "8") (pinfunction "A7_8") (pintype "bidirectional"))
    )
    (net (code "91") (name "PIA-B7") (class "Default")
      (node (ref "CORE-IO") (pin "20") (pinfunction "20_20") (pintype "passive"))
      (node (ref "IC26") (pin "9") (pinfunction "A8_9") (pintype "bidirectional"))
    )
    (net (code "92") (name "RX") (class "Default")
      (node (ref "IC20") (pin "12") (pinfunction "R1OUT_12") (pintype "output"))
      (node (ref "IC21") (pin "2") (pinfunction "RXDATA_2") (pintype "input"))
    )
    (net (code "93") (name "RXD") (class "Default")
      (node (ref "IC20") (pin "13") (pinfunction "R1IN_13") (pintype "input"))
      (node (ref "X1") (pin "3") (pinfunction "3_3") (pintype "passive"))
    )
    (net (code "94") (name "R{slash}~{W}") (class "Default")
      (node (ref "IC17") (pin "34") (pinfunction "R/~{W}_34") (pintype "output"))
      (node (ref "IC21") (pin "13") (pinfunction "R/~{W}_13") (pintype "input"))
      (node (ref "IC22") (pin "27") (pinfunction "~{WE}_27") (pintype "input"))
      (node (ref "IC24") (pin "21") (pinfunction "R/~{W}_21") (pintype "input"))
    )
    (net (code "95") (name "TX") (class "Default")
      (node (ref "IC20") (pin "11") (pinfunction "T1IN_11") (pintype "input"))
      (node (ref "IC21") (pin "6") (pinfunction "TXDATA_6") (pintype "output"))
    )
    (net (code "96") (name "TXD") (class "Default")
      (node (ref "IC20") (pin "14") (pinfunction "T1OUT_14") (pintype "output"))
      (node (ref "X1") (pin "2") (pinfunction "2_2") (pintype "passive"))
    )
    (net (code "97") (name "VCC") (class "Default")
      (node (ref "BYP17") (pin "1") (pinfunction "1_1") (pintype "passive"))
      (node (ref "BYP18") (pin "1") (pinfunction "1_1") (pintype "passive"))
      (node (ref "BYP19") (pin "1") (pinfunction "1_1") (pintype "passive"))
      (node (ref "BYP20") (pin "1") (pinfunction "1_1") (pintype "passive"))
      (node (ref "BYP21") (pin "1") (pinfunction "1_1") (pintype "passive"))
      (node (ref "BYP22") (pin "1") (pinfunction "1_1") (pintype "passive"))
      (node (ref "BYP23") (pin "1") (pinfunction "1_1") (pintype "passive"))
      (node (ref "BYP24") (pin "1") (pinfunction "1_1") (pintype "passive"))
      (node (ref "BYP25") (pin "1") (pinfunction "1_1") (pintype "passive"))
      (node (ref "BYP26") (pin "1") (pinfunction "1_1") (pintype "passive"))
      (node (ref "BYP27") (pin "1") (pinfunction "1_1") (pintype "passive"))
      (node (ref "BYP28") (pin "1") (pinfunction "1_1") (pintype "passive"))
      (node (ref "C10") (pin "1") (pinfunction "1_1") (pintype "passive"))
      (node (ref "CORE-IO") (pin "12") (pinfunction "12_12") (pintype "passive"))
      (node (ref "CORE-IO") (pin "9") (pinfunction "9_9") (pintype "passive"))
      (node (ref "IC17") (pin "35") (pinfunction "VCCSTB_35") (pintype "input"))
      (node (ref "IC17") (pin "36") (pinfunction "RE_36") (pintype "input"))
      (node (ref "IC17") (pin "8") (pinfunction "VCC_8") (pintype "power_in"))
      (node (ref "IC21") (pin "10") (pinfunction "CS1_10") (pintype "input"))
      (node (ref "IC21") (pin "12") (pinfunction "VCC_12") (pintype "power_in"))
      (node (ref "IC21") (pin "8") (pinfunction "CS0_8") (pintype "input"))
      (node (ref "IC22") (pin "26") (pinfunction "CS2_26") (pintype "input"))
      (node (ref "IC22") (pin "28") (pinfunction "VCC_28") (pintype "power_in"))
      (node (ref "IC23") (pin "1") (pinfunction "VPP_1") (pintype "input"))
      (node (ref "IC23") (pin "27") (pinfunction "~{PGM}_27") (pintype "passive"))
      (node (ref "IC23") (pin "28") (pinfunction "VCC_28") (pintype "power_in"))
      (node (ref "IC24") (pin "20") (pinfunction "VCC_20") (pintype "power_in"))
      (node (ref "IC24") (pin "22") (pinfunction "CS0_22") (pintype "input"))
      (node (ref "IC24") (pin "24") (pinfunction "CS1_24") (pintype "input"))
      (node (ref "IC27") (pin "10") (pinfunction "R_10") (pintype "input"))
      (node (ref "IC27") (pin "14") (pinfunction "V+_14") (pintype "power_in"))
      (node (ref "IC27") (pin "4") (pinfunction "R_4") (pintype "input"))
      (node (ref "JP2") (pin "2") (pinfunction "2_2") (pintype "passive"))
      (node (ref "JP4") (pin "2") (pinfunction "2_2") (pintype "passive"))
      (node (ref "R1") (pin "2") (pinfunction "2_2") (pintype "passive"))
      (node (ref "R12") (pin "2") (pinfunction "2_2") (pintype "passive"))
      (node (ref "R14") (pin "2") (pinfunction "2_2") (pintype "passive"))
      (node (ref "R2") (pin "2") (pinfunction "2_2") (pintype "passive"))
      (node (ref "R3") (pin "2") (pinfunction "2_2") (pintype "passive"))
      (node (ref "R5") (pin "2") (pinfunction "2_2") (pintype "passive"))
      (node (ref "R6") (pin "2") (pinfunction "2_2") (pintype "passive"))
      (node (ref "R7") (pin "2") (pinfunction "2_2") (pintype "passive"))
      (node (ref "R8") (pin "2") (pinfunction "2_2") (pintype "passive"))
      (node (ref "R9") (pin "2") (pinfunction "2_2") (pintype "passive"))
    )
    (net (code "98") (name "VMA") (class "Default")
      (node (ref "IC17") (pin "5") (pinfunction "VMA_5") (pintype "output"))
      (node (ref "IC18") (pin "9") (pinfunction "I0_9") (pintype "input"))
    )
    (net (code "99") (name "unconnected-(IC17A-BA-Pad7)") (class "Default")
      (node (ref "IC17") (pin "7") (pinfunction "BA_7") (pintype "output"))
    )
    (net (code "100") (name "unconnected-(IC19A-Y0-Pad15)") (class "Default")
      (node (ref "IC19") (pin "15") (pinfunction "Y0_15") (pintype "output"))
    )
    (net (code "101") (name "unconnected-(IC19A-Y1-Pad14)") (class "Default")
      (node (ref "IC19") (pin "14") (pinfunction "Y1_14") (pintype "output"))
    )
    (net (code "102") (name "unconnected-(IC19A-Y2-Pad13)") (class "Default")
      (node (ref "IC19") (pin "13") (pinfunction "Y2_13") (pintype "output"))
    )
    (net (code "103") (name "unconnected-(IC19A-Y3-Pad12)") (class "Default")
      (node (ref "IC19") (pin "12") (pinfunction "Y3_12") (pintype "output"))
    )
    (net (code "104") (name "unconnected-(IC19A-Y4-Pad11)") (class "Default")
      (node (ref "IC19") (pin "11") (pinfunction "Y4_11") (pintype "output"))
    )
    (net (code "105") (name "unconnected-(IC19A-Y5-Pad10)") (class "Default")
      (node (ref "IC19") (pin "10") (pinfunction "Y5_10") (pintype "output"))
    )
    (net (code "106") (name "unconnected-(IC20A-R2OUT-Pad9)") (class "Default")
      (node (ref "IC20") (pin "9") (pinfunction "R2OUT_9") (pintype "output"))
    )
    (net (code "107") (name "unconnected-(IC22-NC-Pad1)") (class "Default")
      (node (ref "IC22") (pin "1") (pinfunction "NC_1") (pintype "no_connect"))
    )
    (net (code "108") (name "unconnected-(IC28A-Y1-Pad5)") (class "Default")
      (node (ref "IC28") (pin "5") (pinfunction "Y1_5") (pintype "output"))
    )
    (net (code "109") (name "unconnected-(IC28B-Y0-Pad12)") (class "Default")
      (node (ref "IC28") (pin "12") (pinfunction "Y0_12") (pintype "output"))
    )
    (net (code "110") (name "unconnected-(IC28B-Y1-Pad11)") (class "Default")
      (node (ref "IC28") (pin "11") (pinfunction "Y1_11") (pintype "output"))
    )
    (net (code "111") (name "unconnected-(IC28B-Y2-Pad10)") (class "Default")
      (node (ref "IC28") (pin "10") (pinfunction "Y2_10") (pintype "output"))
    )
    (net (code "112") (name "unconnected-(IC28B-Y3-Pad9)") (class "Default")
      (node (ref "IC28") (pin "9") (pinfunction "Y3_9") (pintype "output"))
    )
    (net (code "113") (name "unconnected-(X1-Pad1)") (class "Default")
      (node (ref "X1") (pin "1") (pinfunction "1_1") (pintype "passive"))
    )
    (net (code "114") (name "unconnected-(X1-Pad9)") (class "Default")
      (node (ref "X1") (pin "9") (pinfunction "9_9") (pintype "passive"))
    )
    (net (code "115") (name "~{89AB}") (class "Default")
      (node (ref "IC22") (pin "20") (pinfunction "~{CS1}_20") (pintype "input"))
      (node (ref "IC22") (pin "22") (pinfunction "~{OE}_22") (pintype "input"))
      (node (ref "IC28") (pin "6") (pinfunction "Y2_6") (pintype "output"))
    )
    (net (code "116") (name "~{CDEF}") (class "Default")
      (node (ref "IC23") (pin "20") (pinfunction "~{CE}_20") (pintype "input"))
      (node (ref "IC23") (pin "22") (pinfunction "~{OE}_22") (pintype "input"))
      (node (ref "IC28") (pin "7") (pinfunction "Y3_7") (pintype "output"))
    )
    (net (code "117") (name "~{HLT}") (class "Default")
      (node (ref "IC17") (pin "2") (pinfunction "HALT_2") (pintype "input"))
      (node (ref "R5") (pin "1") (pinfunction "1_1") (pintype "passive"))
    )
    (net (code "118") (name "~{IO-E}") (class "Default")
      (node (ref "IC19") (pin "9") (pinfunction "Y6_9") (pintype "output"))
      (node (ref "IC24") (pin "23") (pinfunction "CS2_23") (pintype "input"))
    )
    (net (code "119") (name "~{IO-F}") (class "Default")
      (node (ref "IC19") (pin "7") (pinfunction "Y7_7") (pintype "output"))
      (node (ref "IC21") (pin "9") (pinfunction "CS2_9") (pintype "input"))
    )
    (net (code "120") (name "~{IRQ}") (class "Default")
      (node (ref "IC17") (pin "4") (pinfunction "IRQ_4") (pintype "input"))
      (node (ref "IC24") (pin "37") (pinfunction "IRQB_37") (pintype "open_collector"))
      (node (ref "IC24") (pin "38") (pinfunction "IRQA_38") (pintype "open_collector"))
      (node (ref "R7") (pin "1") (pinfunction "1_1") (pintype "passive"))
    )
    (net (code "121") (name "~{NMI}") (class "Default")
      (node (ref "IC17") (pin "6") (pinfunction "NMI_6") (pintype "input"))
      (node (ref "IC21") (pin "7") (pinfunction "IRQ_7") (pintype "output"))
      (node (ref "R6") (pin "1") (pinfunction "1_1") (pintype "passive"))
    )
    (net (code "122") (name "~{RST}") (class "Default")
      (node (ref "IC17") (pin "40") (pinfunction "RESET_40") (pintype "input"))
      (node (ref "IC18") (pin "6") (pinfunction "O_6") (pintype "output"))
      (node (ref "IC24") (pin "34") (pinfunction "RESET_34") (pintype "input"))
    )
  )
)
